# tmc2130-driver-arduino-shield-v3.net
KiCad netlist of a schematic drawn in EAGLE
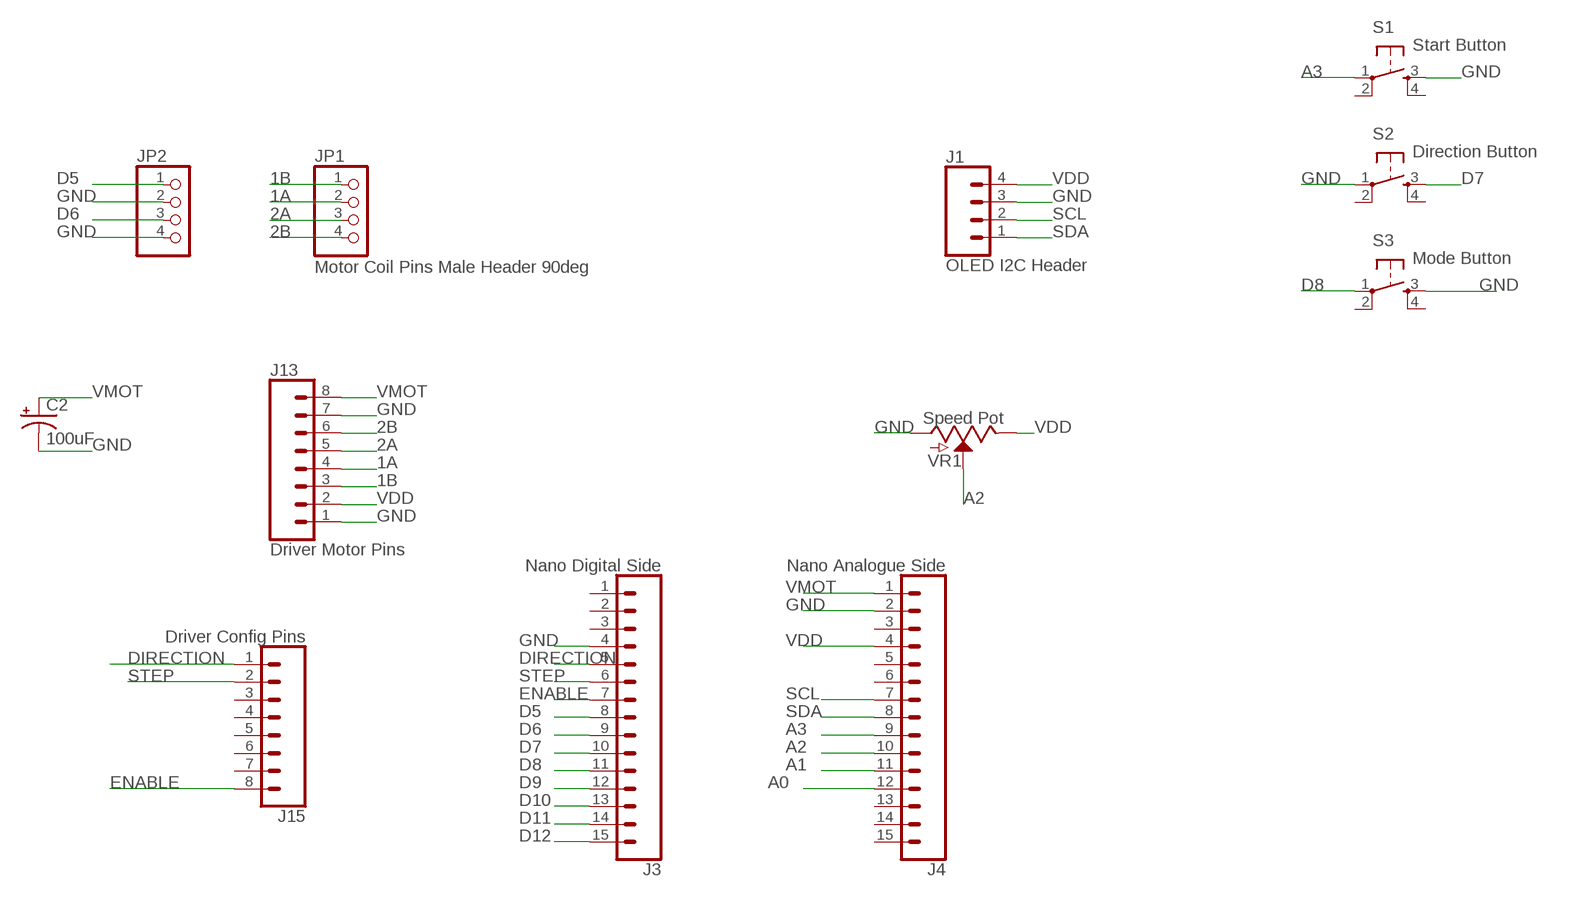
[diagram p0: schematic, sheet 1]

(export (version "E")
  (design (tool "Eeschema 10.0.6"))
  (components
    (comp (ref "C2")
      (value "100uF")
      (footprint "eagle-import:CPOL-RADIAL-2.5MM-6.5MM")
      (libsource (lib "eagle-import") (part "100UF-POLAR-RADIAL-2.5MM-25V-20%"))
    )
    (comp (ref "J1")
      (value "OLED I2C Header")
      (footprint "eagle-import:1X04_LONGPADS")
      (libsource (lib "eagle-import") (part "CONN_04LONGPADS"))
    )
    (comp (ref "J3")
      (value "Nano Digital Side")
      (footprint "eagle-import:1X15")
      (libsource (lib "eagle-import") (part "CONN_15"))
    )
    (comp (ref "J4")
      (value "Nano Analogue Side")
      (footprint "eagle-import:1X15")
      (libsource (lib "eagle-import") (part "CONN_15"))
    )
    (comp (ref "J13")
      (value "Driver Motor Pins")
      (footprint "eagle-import:1X08_LONGPADS")
      (libsource (lib "eagle-import") (part "CONN_08LONGPADS"))
    )
    (comp (ref "J15")
      (value "Driver Config Pins")
      (footprint "eagle-import:1X08_LONGPADS")
      (libsource (lib "eagle-import") (part "CONN_08LONGPADS"))
    )
    (comp (ref "JP1")
      (value "Motor Coil Pins Male Header 90deg")
      (footprint "eagle-import:1X04_90")
      (libsource (lib "eagle-import") (part "PINHD-1X4/90"))
    )
    (comp (ref "JP2")
      (value "PINHD-1X4/90")
      (footprint "eagle-import:1X04_90")
      (libsource (lib "eagle-import") (part "PINHD-1X4/90"))
    )
    (comp (ref "S1")
      (value "Start Button")
      (footprint "eagle-import:6MM_SWITCH")
      (libsource (lib "eagle-import") (part "6MM_SWITCH6MM_SWITCH"))
    )
    (comp (ref "S2")
      (value "Direction Button")
      (footprint "eagle-import:6MM_SWITCH")
      (libsource (lib "eagle-import") (part "6MM_SWITCH6MM_SWITCH"))
    )
    (comp (ref "S3")
      (value "Mode Button")
      (footprint "eagle-import:6MM_SWITCH")
      (libsource (lib "eagle-import") (part "6MM_SWITCH6MM_SWITCH"))
    )
    (comp (ref "VR1")
      (value "Speed Pot")
      (footprint "eagle-import:POT-PTH-ALPS")
      (libsource (lib "eagle-import") (part "POTENTIOMETER-PTH-9MM-1/20W-20%"))
    )
  )
  (nets
    (net (code "1") (name "/1A") (class "Default")
      (node (ref "J13") (pin "4") (pinfunction "4_4") (pintype "passive"))
      (node (ref "JP1") (pin "2") (pinfunction "2_2") (pintype "passive"))
    )
    (net (code "2") (name "/1B") (class "Default")
      (node (ref "J13") (pin "3") (pinfunction "3_3") (pintype "passive"))
      (node (ref "JP1") (pin "1") (pinfunction "1_1") (pintype "passive"))
    )
    (net (code "3") (name "/2A") (class "Default")
      (node (ref "J13") (pin "5") (pinfunction "5_5") (pintype "passive"))
      (node (ref "JP1") (pin "3") (pinfunction "3_3") (pintype "passive"))
    )
    (net (code "4") (name "/2B") (class "Default")
      (node (ref "J13") (pin "6") (pinfunction "6_6") (pintype "passive"))
      (node (ref "JP1") (pin "4") (pinfunction "4_4") (pintype "passive"))
    )
    (net (code "5") (name "/A0") (class "Default")
      (node (ref "J4") (pin "12") (pinfunction "12_12") (pintype "passive"))
    )
    (net (code "6") (name "/A1") (class "Default")
      (node (ref "J4") (pin "11") (pinfunction "11_11") (pintype "passive"))
    )
    (net (code "7") (name "/A2") (class "Default")
      (node (ref "J4") (pin "10") (pinfunction "10_10") (pintype "passive"))
      (node (ref "VR1") (pin "P$2") (pinfunction "S_P$2") (pintype "passive"))
    )
    (net (code "8") (name "/A3") (class "Default")
      (node (ref "J4") (pin "9") (pinfunction "9_9") (pintype "passive"))
      (node (ref "S1") (pin "1") (pinfunction "P_1") (pintype "passive"))
    )
    (net (code "9") (name "/D5") (class "Default")
      (node (ref "J3") (pin "8") (pinfunction "8_8") (pintype "passive"))
      (node (ref "JP2") (pin "1") (pinfunction "1_1") (pintype "passive"))
    )
    (net (code "10") (name "/D6") (class "Default")
      (node (ref "J3") (pin "9") (pinfunction "9_9") (pintype "passive"))
      (node (ref "JP2") (pin "3") (pinfunction "3_3") (pintype "passive"))
    )
    (net (code "11") (name "/D7") (class "Default")
      (node (ref "J3") (pin "10") (pinfunction "10_10") (pintype "passive"))
      (node (ref "S2") (pin "3") (pinfunction "S_3") (pintype "passive"))
    )
    (net (code "12") (name "/D8") (class "Default")
      (node (ref "J3") (pin "11") (pinfunction "11_11") (pintype "passive"))
      (node (ref "S3") (pin "1") (pinfunction "P_1") (pintype "passive"))
    )
    (net (code "13") (name "/D9") (class "Default")
      (node (ref "J3") (pin "12") (pinfunction "12_12") (pintype "passive"))
    )
    (net (code "14") (name "/D10") (class "Default")
      (node (ref "J3") (pin "13") (pinfunction "13_13") (pintype "passive"))
    )
    (net (code "15") (name "/D11") (class "Default")
      (node (ref "J3") (pin "14") (pinfunction "14_14") (pintype "passive"))
    )
    (net (code "16") (name "/D12") (class "Default")
      (node (ref "J3") (pin "15") (pinfunction "15_15") (pintype "passive"))
    )
    (net (code "17") (name "/DIRECTION") (class "Default")
      (node (ref "J15") (pin "1") (pinfunction "1_1") (pintype "passive"))
      (node (ref "J3") (pin "5") (pinfunction "5_5") (pintype "passive"))
    )
    (net (code "18") (name "/ENABLE") (class "Default")
      (node (ref "J15") (pin "8") (pinfunction "8_8") (pintype "passive"))
      (node (ref "J3") (pin "7") (pinfunction "7_7") (pintype "passive"))
    )
    (net (code "19") (name "/GND") (class "Default")
      (node (ref "C2") (pin "2") (pinfunction "-_2") (pintype "passive"))
      (node (ref "J1") (pin "3") (pinfunction "3_3") (pintype "passive"))
      (node (ref "J13") (pin "1") (pinfunction "1_1") (pintype "passive"))
      (node (ref "J13") (pin "7") (pinfunction "7_7") (pintype "passive"))
      (node (ref "J3") (pin "4") (pinfunction "4_4") (pintype "passive"))
      (node (ref "J4") (pin "2") (pinfunction "2_2") (pintype "passive"))
      (node (ref "JP2") (pin "2") (pinfunction "2_2") (pintype "passive"))
      (node (ref "JP2") (pin "4") (pinfunction "4_4") (pintype "passive"))
      (node (ref "S1") (pin "3") (pinfunction "S_3") (pintype "passive"))
      (node (ref "S2") (pin "1") (pinfunction "P_1") (pintype "passive"))
      (node (ref "S3") (pin "3") (pinfunction "S_3") (pintype "passive"))
      (node (ref "VR1") (pin "P$3") (pinfunction "A_P$3") (pintype "passive"))
    )
    (net (code "20") (name "/SCL") (class "Default")
      (node (ref "J1") (pin "2") (pinfunction "2_2") (pintype "passive"))
      (node (ref "J4") (pin "7") (pinfunction "7_7") (pintype "passive"))
    )
    (net (code "21") (name "/SDA") (class "Default")
      (node (ref "J1") (pin "1") (pinfunction "1_1") (pintype "passive"))
      (node (ref "J4") (pin "8") (pinfunction "8_8") (pintype "passive"))
    )
    (net (code "22") (name "/STEP") (class "Default")
      (node (ref "J15") (pin "2") (pinfunction "2_2") (pintype "passive"))
      (node (ref "J3") (pin "6") (pinfunction "6_6") (pintype "passive"))
    )
    (net (code "23") (name "/VDD") (class "Default")
      (node (ref "J1") (pin "4") (pinfunction "4_4") (pintype "passive"))
      (node (ref "J13") (pin "2") (pinfunction "2_2") (pintype "passive"))
      (node (ref "J4") (pin "4") (pinfunction "4_4") (pintype "passive"))
      (node (ref "VR1") (pin "P$1") (pinfunction "E_P$1") (pintype "passive"))
    )
    (net (code "24") (name "/VMOT") (class "Default")
      (node (ref "C2") (pin "1") (pinfunction "+_1") (pintype "passive"))
      (node (ref "J13") (pin "8") (pinfunction "8_8") (pintype "passive"))
      (node (ref "J4") (pin "1") (pinfunction "1_1") (pintype "passive"))
    )
    (net (code "25") (name "unconnected-(J3-Pad1)") (class "Default")
      (node (ref "J3") (pin "1") (pinfunction "1_1") (pintype "passive"))
    )
    (net (code "26") (name "unconnected-(J3-Pad2)") (class "Default")
      (node (ref "J3") (pin "2") (pinfunction "2_2") (pintype "passive"))
    )
    (net (code "27") (name "unconnected-(J3-Pad3)") (class "Default")
      (node (ref "J3") (pin "3") (pinfunction "3_3") (pintype "passive"))
    )
    (net (code "28") (name "unconnected-(J4-Pad3)") (class "Default")
      (node (ref "J4") (pin "3") (pinfunction "3_3") (pintype "passive"))
    )
    (net (code "29") (name "unconnected-(J4-Pad5)") (class "Default")
      (node (ref "J4") (pin "5") (pinfunction "5_5") (pintype "passive"))
    )
    (net (code "30") (name "unconnected-(J4-Pad6)") (class "Default")
      (node (ref "J4") (pin "6") (pinfunction "6_6") (pintype "passive"))
    )
    (net (code "31") (name "unconnected-(J4-Pad13)") (class "Default")
      (node (ref "J4") (pin "13") (pinfunction "13_13") (pintype "passive"))
    )
    (net (code "32") (name "unconnected-(J4-Pad14)") (class "Default")
      (node (ref "J4") (pin "14") (pinfunction "14_14") (pintype "passive"))
    )
    (net (code "33") (name "unconnected-(J4-Pad15)") (class "Default")
      (node (ref "J4") (pin "15") (pinfunction "15_15") (pintype "passive"))
    )
    (net (code "34") (name "unconnected-(J15-Pad3)") (class "Default")
      (node (ref "J15") (pin "3") (pinfunction "3_3") (pintype "passive"))
    )
    (net (code "35") (name "unconnected-(J15-Pad4)") (class "Default")
      (node (ref "J15") (pin "4") (pinfunction "4_4") (pintype "passive"))
    )
    (net (code "36") (name "unconnected-(J15-Pad5)") (class "Default")
      (node (ref "J15") (pin "5") (pinfunction "5_5") (pintype "passive"))
    )
    (net (code "37") (name "unconnected-(J15-Pad6)") (class "Default")
      (node (ref "J15") (pin "6") (pinfunction "6_6") (pintype "passive"))
    )
    (net (code "38") (name "unconnected-(J15-Pad7)") (class "Default")
      (node (ref "J15") (pin "7") (pinfunction "7_7") (pintype "passive"))
    )
    (net (code "39") (name "unconnected-(S1-P1-Pad2)") (class "Default")
      (node (ref "S1") (pin "2") (pinfunction "P1_2") (pintype "passive"))
    )
    (net (code "40") (name "unconnected-(S1-S1-Pad4)") (class "Default")
      (node (ref "S1") (pin "4") (pinfunction "S1_4") (pintype "passive"))
    )
    (net (code "41") (name "unconnected-(S2-P1-Pad2)") (class "Default")
      (node (ref "S2") (pin "2") (pinfunction "P1_2") (pintype "passive"))
    )
    (net (code "42") (name "unconnected-(S2-S1-Pad4)") (class "Default")
      (node (ref "S2") (pin "4") (pinfunction "S1_4") (pintype "passive"))
    )
    (net (code "43") (name "unconnected-(S3-P1-Pad2)") (class "Default")
      (node (ref "S3") (pin "2") (pinfunction "P1_2") (pintype "passive"))
    )
    (net (code "44") (name "unconnected-(S3-S1-Pad4)") (class "Default")
      (node (ref "S3") (pin "4") (pinfunction "S1_4") (pintype "passive"))
    )
  )
)
